# SinglePhaseBoard.net
KiCad netlist of a schematic drawn in Altium Designer
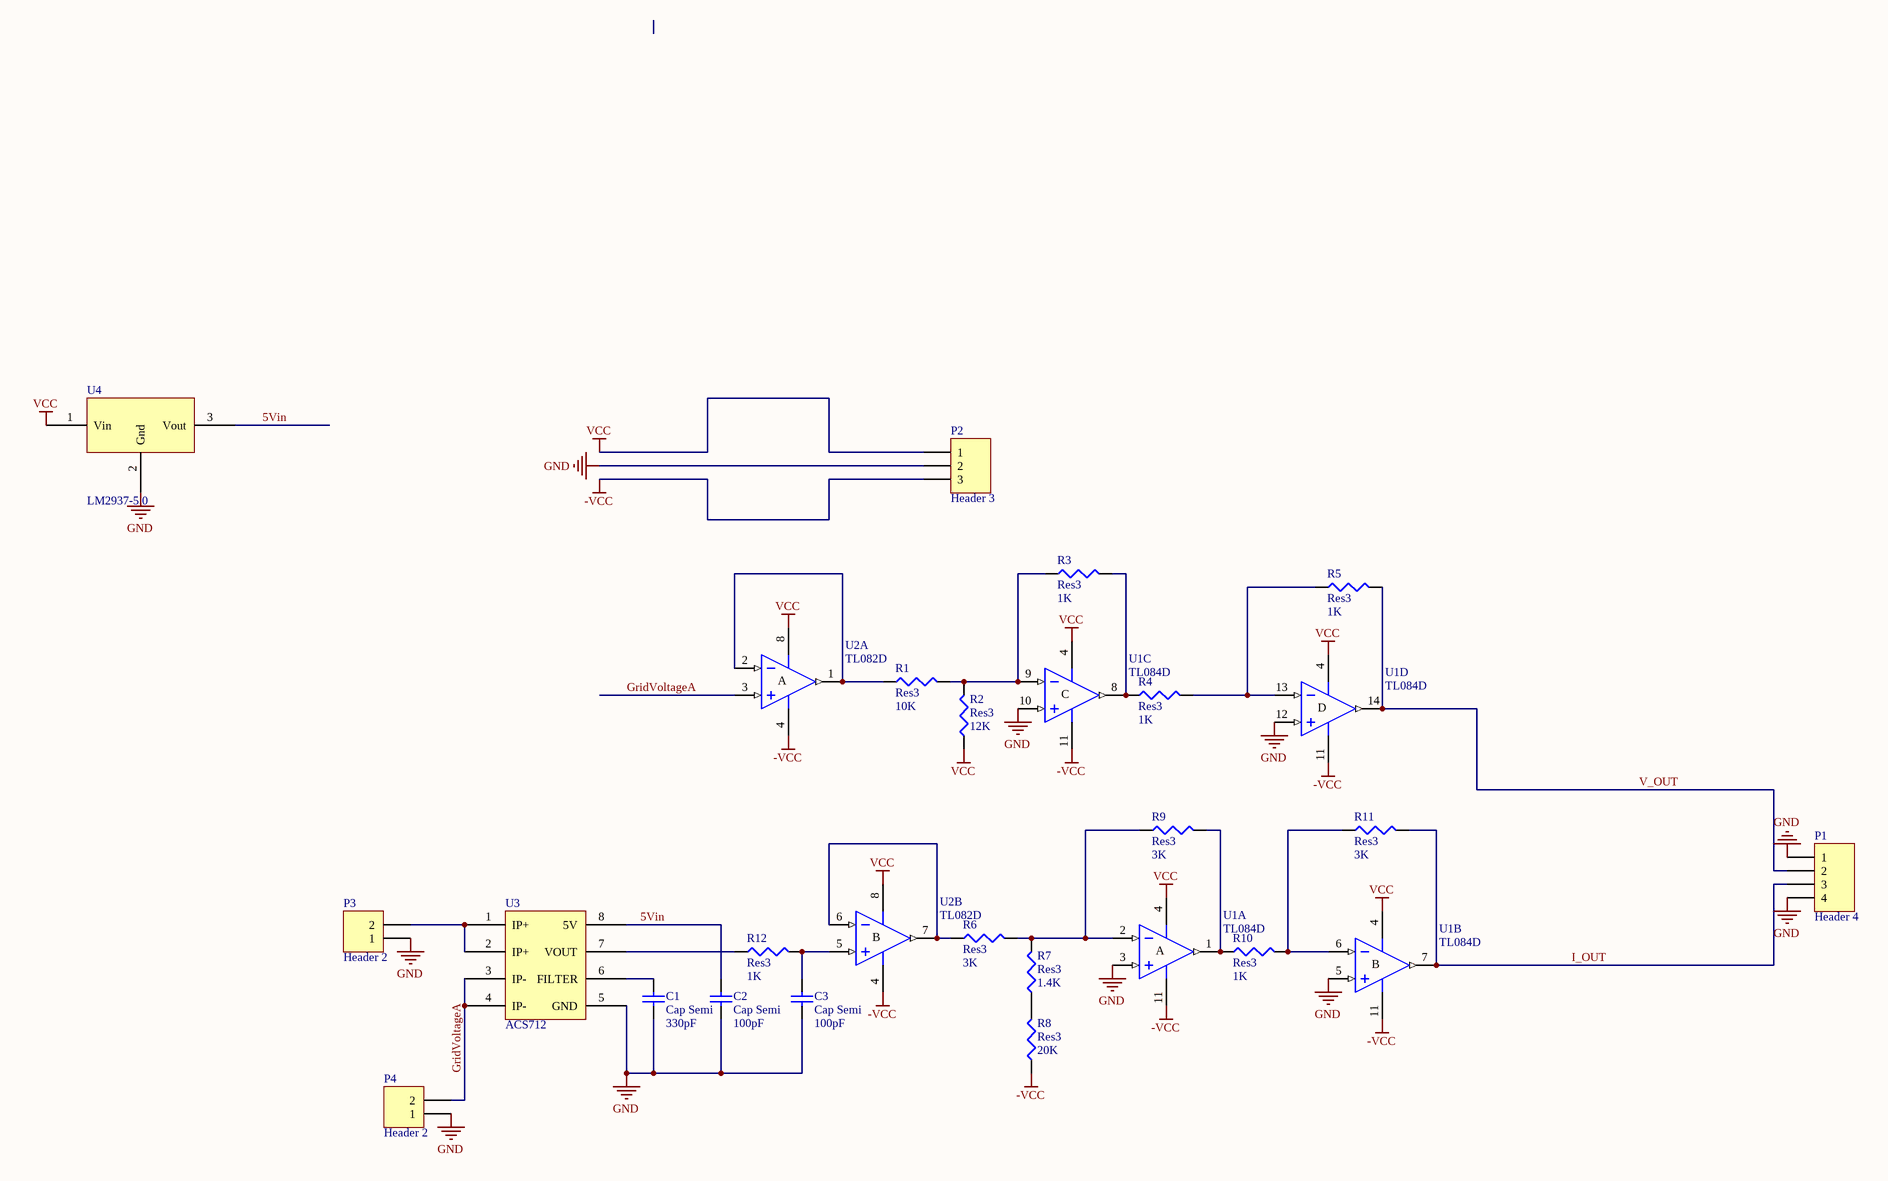
[diagram p0: SinglePhaseBoard.SchDoc]

(export (version "E")
  (design (tool "Eeschema 10.0.6"))
  (components
    (comp (ref "C1")
      (value "Cap Semi")
      (footprint "CAP0805")
      (description "Capacitor (Semiconductor SIM Model)")
      (fields (field (name "ALTIUM_VALUE") "330pF") (field (name "PUBLISHER") "Altium Limited"))
      (libsource (lib "Miscellaneous Devices") (part "Cap Semi"))
    )
    (comp (ref "C2")
      (value "Cap Semi")
      (footprint "CAP0402")
      (description "Capacitor (Semiconductor SIM Model)")
      (fields (field (name "ALTIUM_VALUE") "100pF") (field (name "PUBLISHER") "Altium Limited"))
      (libsource (lib "Miscellaneous Devices") (part "Cap Semi"))
    )
    (comp (ref "C3")
      (value "Cap Semi")
      (footprint "CAP0402")
      (description "Capacitor (Semiconductor SIM Model)")
      (fields (field (name "ALTIUM_VALUE") "100pF") (field (name "PUBLISHER") "Altium Limited"))
      (libsource (lib "Miscellaneous Devices") (part "Cap Semi"))
    )
    (comp (ref "P1")
      (value "Header 4")
      (footprint "HDR1X4")
      (description "Header, 4-Pin")
      (fields (field (name "PUBLISHER") "Altium Limited"))
      (libsource (lib "Miscellaneous Connectors") (part "Header 4"))
    )
    (comp (ref "P2")
      (value "Header 3")
      (footprint "HDR1X3")
      (description "Header, 3-Pin")
      (fields (field (name "PUBLISHER") "Altium Limited"))
      (libsource (lib "Miscellaneous Connectors") (part "Header 3"))
    )
    (comp (ref "P3")
      (value "Header 2")
      (footprint "HDR1X2")
      (description "Header, 2-Pin")
      (fields (field (name "PUBLISHER") "Altium Limited"))
      (libsource (lib "Miscellaneous Connectors") (part "Header 2"))
    )
    (comp (ref "P4")
      (value "Header 2")
      (footprint "HDR1X2")
      (description "Header, 2-Pin")
      (fields (field (name "PUBLISHER") "Altium Limited"))
      (libsource (lib "Miscellaneous Connectors") (part "Header 2"))
    )
    (comp (ref "R1")
      (value "Res3")
      (footprint "RESC1608X06N")
      (description "Resistor")
      (fields (field (name "ALTIUM_VALUE") "10K") (field (name "PUBLISHER") "Altium Limited"))
      (libsource (lib "Miscellaneous Devices") (part "Res3"))
    )
    (comp (ref "R2")
      (value "Res3")
      (footprint "RESC1608X06N")
      (description "Resistor")
      (fields (field (name "ALTIUM_VALUE") "12K") (field (name "PUBLISHER") "Altium Limited"))
      (libsource (lib "Miscellaneous Devices") (part "Res3"))
    )
    (comp (ref "R3")
      (value "Res3")
      (footprint "RESC1608X06N")
      (description "Resistor")
      (fields (field (name "ALTIUM_VALUE") "1K") (field (name "PUBLISHER") "Altium Limited"))
      (libsource (lib "Miscellaneous Devices") (part "Res3"))
    )
    (comp (ref "R4")
      (value "Res3")
      (footprint "RESC1608X06N")
      (description "Resistor")
      (fields (field (name "ALTIUM_VALUE") "1K") (field (name "PUBLISHER") "Altium Limited"))
      (libsource (lib "Miscellaneous Devices") (part "Res3"))
    )
    (comp (ref "R5")
      (value "Res3")
      (footprint "RESC1608X06N")
      (description "Resistor")
      (fields (field (name "ALTIUM_VALUE") "1K") (field (name "PUBLISHER") "Altium Limited"))
      (libsource (lib "Miscellaneous Devices") (part "Res3"))
    )
    (comp (ref "R6")
      (value "Res3")
      (footprint "RESC1608X06N")
      (description "Resistor")
      (fields (field (name "ALTIUM_VALUE") "3K") (field (name "PUBLISHER") "Altium Limited"))
      (libsource (lib "Miscellaneous Devices") (part "Res3"))
    )
    (comp (ref "R7")
      (value "Res3")
      (footprint "RESC1608X06N")
      (description "Resistor")
      (fields (field (name "ALTIUM_VALUE") "1.4K") (field (name "PUBLISHER") "Altium Limited"))
      (libsource (lib "Miscellaneous Devices") (part "Res3"))
    )
    (comp (ref "R8")
      (value "Res3")
      (footprint "RESC1608X06N")
      (description "Resistor")
      (fields (field (name "ALTIUM_VALUE") "20K") (field (name "PUBLISHER") "Altium Limited"))
      (libsource (lib "Miscellaneous Devices") (part "Res3"))
    )
    (comp (ref "R9")
      (value "Res3")
      (footprint "RESC1608X06N")
      (description "Resistor")
      (fields (field (name "ALTIUM_VALUE") "3K") (field (name "PUBLISHER") "Altium Limited"))
      (libsource (lib "Miscellaneous Devices") (part "Res3"))
    )
    (comp (ref "R10")
      (value "Res3")
      (footprint "RESC1608X06N")
      (description "Resistor")
      (fields (field (name "ALTIUM_VALUE") "1K") (field (name "PUBLISHER") "Altium Limited"))
      (libsource (lib "Miscellaneous Devices") (part "Res3"))
    )
    (comp (ref "R11")
      (value "Res3")
      (footprint "RESC1608X06N")
      (description "Resistor")
      (fields (field (name "ALTIUM_VALUE") "3K") (field (name "PUBLISHER") "Altium Limited"))
      (libsource (lib "Miscellaneous Devices") (part "Res3"))
    )
    (comp (ref "R12")
      (value "Res3")
      (footprint "RESC1608X06N")
      (description "Resistor")
      (fields (field (name "ALTIUM_VALUE") "1K") (field (name "PUBLISHER") "Altium Limited"))
      (libsource (lib "Miscellaneous Devices") (part "Res3"))
    )
    (comp (ref "U1")
      (value "TL084D")
      (footprint "D014_N")
      (description "JFET-Input Operational Amplifier")
      (fields (field (name "PUBLISHER") "Altium Limited"))
      (libsource (lib "TI Operational Amplifier") (part "TL084D"))
    )
    (comp (ref "U2")
      (value "TL082D")
      (footprint "D008_L")
      (description "JFET-Input Operational Amplifier")
      (fields (field (name "PUBLISHER") "Altium Limited"))
      (libsource (lib "TI Operational Amplifier") (part "TL082D"))
    )
    (comp (ref "U3")
      (value "ACS712")
      (footprint "SOIC127P620X175-8N")
      (libsource (lib "ACS712") (part "ACS712"))
    )
    (comp (ref "U4")
      (value "LM2937-5.0")
      (footprint "5Vregulator:TO254P1258X464-4N")
      (description "5V voltage regulator")
      (libsource (lib "LM2937ESX") (part "LM2937-5.0"))
    )
  )
  (nets
    (net (code "1") (name "-VCC") (class "Default")
      (node (ref "P2") (pin "3") (pinfunction "3_3") (pintype "passive"))
      (node (ref "R8") (pin "1") (pinfunction "1_1") (pintype "passive"))
      (node (ref "U1") (pin "11") (pinfunction "V-_11") (pintype "power_in"))
      (node (ref "U2") (pin "4") (pinfunction "V-_4") (pintype "power_in"))
    )
    (net (code "2") (name "/5Vin") (class "Default")
      (node (ref "C2") (pin "2") (pinfunction "2_2") (pintype "passive"))
      (node (ref "U3") (pin "8") (pinfunction "5V_8") (pintype "power_in"))
      (node (ref "U4") (pin "3") (pinfunction "Vout_3") (pintype "passive"))
    )
    (net (code "3") (name "/GridVoltageA") (class "Default")
      (node (ref "P4") (pin "2") (pinfunction "2_2") (pintype "passive"))
      (node (ref "U2") (pin "3") (pinfunction "IN+_3") (pintype "input"))
      (node (ref "U3") (pin "3") (pinfunction "IP-_3") (pintype "passive"))
      (node (ref "U3") (pin "4") (pinfunction "IP-_4") (pintype "passive"))
    )
    (net (code "4") (name "/I_OUT") (class "Default")
      (node (ref "P1") (pin "3") (pinfunction "3_3") (pintype "passive"))
      (node (ref "R11") (pin "2") (pinfunction "2_2") (pintype "passive"))
      (node (ref "U1") (pin "7") (pinfunction "OUT_7") (pintype "output"))
    )
    (net (code "5") (name "/V_OUT") (class "Default")
      (node (ref "P1") (pin "2") (pinfunction "2_2") (pintype "passive"))
      (node (ref "R5") (pin "2") (pinfunction "2_2") (pintype "passive"))
      (node (ref "U1") (pin "14") (pinfunction "OUT_14") (pintype "output"))
    )
    (net (code "6") (name "GND") (class "Default")
      (node (ref "C1") (pin "2") (pinfunction "2_2") (pintype "passive"))
      (node (ref "C2") (pin "1") (pinfunction "1_1") (pintype "passive"))
      (node (ref "C3") (pin "1") (pinfunction "1_1") (pintype "passive"))
      (node (ref "P1") (pin "1") (pinfunction "1_1") (pintype "passive"))
      (node (ref "P1") (pin "4") (pinfunction "4_4") (pintype "passive"))
      (node (ref "P2") (pin "2") (pinfunction "2_2") (pintype "passive"))
      (node (ref "P3") (pin "1") (pinfunction "1_1") (pintype "passive"))
      (node (ref "P4") (pin "1") (pinfunction "1_1") (pintype "passive"))
      (node (ref "U1") (pin "10") (pinfunction "IN+_10") (pintype "input"))
      (node (ref "U1") (pin "12") (pinfunction "IN+_12") (pintype "input"))
      (node (ref "U1") (pin "3") (pinfunction "IN+_3") (pintype "input"))
      (node (ref "U1") (pin "5") (pinfunction "IN+_5") (pintype "input"))
      (node (ref "U3") (pin "5") (pinfunction "GND_5") (pintype "power_in"))
      (node (ref "U4") (pin "2") (pinfunction "Gnd_2") (pintype "passive"))
    )
    (net (code "7") (name "Net-(P3-Pad2)") (class "Default")
      (node (ref "P3") (pin "2") (pinfunction "2_2") (pintype "passive"))
      (node (ref "U3") (pin "1") (pinfunction "IP+_1") (pintype "passive"))
      (node (ref "U3") (pin "2") (pinfunction "IP+_2") (pintype "passive"))
    )
    (net (code "8") (name "Net-(R7-Pad1)") (class "Default")
      (node (ref "R7") (pin "1") (pinfunction "1_1") (pintype "passive"))
      (node (ref "R8") (pin "2") (pinfunction "2_2") (pintype "passive"))
    )
    (net (code "9") (name "Net-(U1A-IN-)") (class "Default")
      (node (ref "R6") (pin "2") (pinfunction "2_2") (pintype "passive"))
      (node (ref "R7") (pin "2") (pinfunction "2_2") (pintype "passive"))
      (node (ref "R9") (pin "1") (pinfunction "1_1") (pintype "passive"))
      (node (ref "U1") (pin "2") (pinfunction "IN-_2") (pintype "input"))
    )
    (net (code "10") (name "Net-(U1A-OUT)") (class "Default")
      (node (ref "R10") (pin "1") (pinfunction "1_1") (pintype "passive"))
      (node (ref "R9") (pin "2") (pinfunction "2_2") (pintype "passive"))
      (node (ref "U1") (pin "1") (pinfunction "OUT_1") (pintype "output"))
    )
    (net (code "11") (name "Net-(U1B-IN-)") (class "Default")
      (node (ref "R10") (pin "2") (pinfunction "2_2") (pintype "passive"))
      (node (ref "R11") (pin "1") (pinfunction "1_1") (pintype "passive"))
      (node (ref "U1") (pin "6") (pinfunction "IN-_6") (pintype "input"))
    )
    (net (code "12") (name "Net-(U1C-IN-)") (class "Default")
      (node (ref "R1") (pin "2") (pinfunction "2_2") (pintype "passive"))
      (node (ref "R2") (pin "2") (pinfunction "2_2") (pintype "passive"))
      (node (ref "R3") (pin "1") (pinfunction "1_1") (pintype "passive"))
      (node (ref "U1") (pin "9") (pinfunction "IN-_9") (pintype "input"))
    )
    (net (code "13") (name "Net-(U1C-OUT)") (class "Default")
      (node (ref "R3") (pin "2") (pinfunction "2_2") (pintype "passive"))
      (node (ref "R4") (pin "1") (pinfunction "1_1") (pintype "passive"))
      (node (ref "U1") (pin "8") (pinfunction "OUT_8") (pintype "output"))
    )
    (net (code "14") (name "Net-(U1D-IN-)") (class "Default")
      (node (ref "R4") (pin "2") (pinfunction "2_2") (pintype "passive"))
      (node (ref "R5") (pin "1") (pinfunction "1_1") (pintype "passive"))
      (node (ref "U1") (pin "13") (pinfunction "IN-_13") (pintype "input"))
    )
    (net (code "15") (name "Net-(U2A-IN-)") (class "Default")
      (node (ref "R1") (pin "1") (pinfunction "1_1") (pintype "passive"))
      (node (ref "U2") (pin "1") (pinfunction "OUT_1") (pintype "output"))
      (node (ref "U2") (pin "2") (pinfunction "IN-_2") (pintype "input"))
    )
    (net (code "16") (name "Net-(U2B-IN+)") (class "Default")
      (node (ref "C3") (pin "2") (pinfunction "2_2") (pintype "passive"))
      (node (ref "R12") (pin "2") (pinfunction "2_2") (pintype "passive"))
      (node (ref "U2") (pin "5") (pinfunction "IN+_5") (pintype "input"))
    )
    (net (code "17") (name "Net-(U2B-IN-)") (class "Default")
      (node (ref "R6") (pin "1") (pinfunction "1_1") (pintype "passive"))
      (node (ref "U2") (pin "6") (pinfunction "IN-_6") (pintype "input"))
      (node (ref "U2") (pin "7") (pinfunction "OUT_7") (pintype "output"))
    )
    (net (code "18") (name "Net-(U3-FILTER)") (class "Default")
      (node (ref "C1") (pin "1") (pinfunction "1_1") (pintype "passive"))
      (node (ref "U3") (pin "6") (pinfunction "FILTER_6") (pintype "passive"))
    )
    (net (code "19") (name "Net-(U3-VOUT)") (class "Default")
      (node (ref "R12") (pin "1") (pinfunction "1_1") (pintype "passive"))
      (node (ref "U3") (pin "7") (pinfunction "VOUT_7") (pintype "passive"))
    )
    (net (code "20") (name "VCC") (class "Default")
      (node (ref "P2") (pin "1") (pinfunction "1_1") (pintype "passive"))
      (node (ref "R2") (pin "1") (pinfunction "1_1") (pintype "passive"))
      (node (ref "U1") (pin "4") (pinfunction "V+_4") (pintype "power_in"))
      (node (ref "U2") (pin "8") (pinfunction "V+_8") (pintype "power_in"))
      (node (ref "U4") (pin "1") (pinfunction "Vin_1") (pintype "passive"))
    )
  )
)
